# UART_MUX.net
KiCad netlist of a schematic drawn in Altium Designer
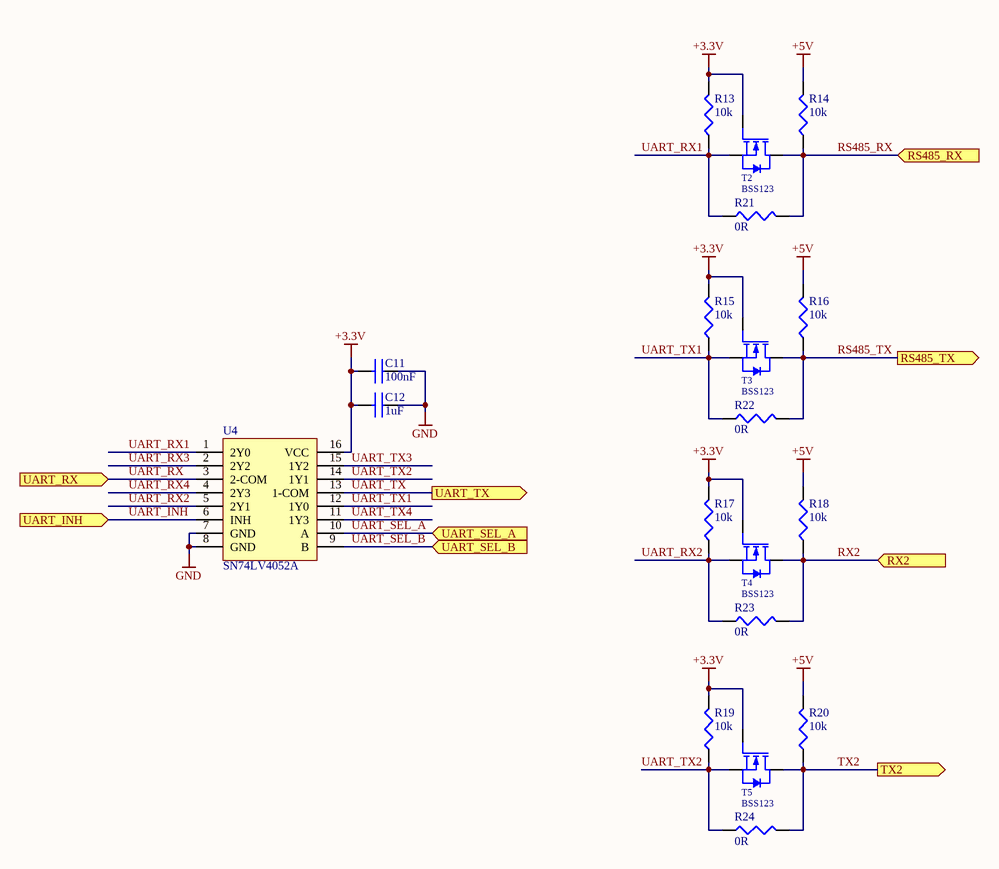
[diagram p0: UART_MUX.SchDoc]

(export (version "E")
  (design (tool "Eeschema 10.0.6"))
  (components
    (comp (ref "C11")
      (value "100nF")
      (footprint "CAP0603")
      (description "MURATA - GRM188R71C104KA01J - CAP, MLCC, X7R, 0.1UF, 16V, 0603")
      (fields
        (field (name "MANUFACTURER") "MURATA")
        (field (name "MANUFACTURER PART NUMBER") "GRM188R71C104KA01J")
      )
      (libsource (lib "Passive") (part "C - 100nF"))
    )
    (comp (ref "C12")
      (value "1uF")
      (footprint "CAP0603")
      (description "MURATA - GRM188R61H105KAALD - CAP, MLCC, X5R, 1UF, 50V, 0603")
      (fields
        (field (name "MANUFACTURER") "MURATA")
        (field (name "MANUFACTURER PART NUMBER") "GRM188R61H105KAALD")
      )
      (libsource (lib "Passive") (part "C - 1uF"))
    )
    (comp (ref "R13")
      (value "10k")
      (footprint "RES0603")
      (description "MULTICOMP - MCMR06X103 JTL - RES, CERAMIC, 10K, 5%, 0.1W, 0603")
      (fields
        (field (name "MANUFACTURER") "MULTICOMP")
        (field (name "MANUFACTURER PART NUMBER") "MCMR06X103 JTL")
      )
      (libsource (lib "Passive") (part "R - 10k"))
    )
    (comp (ref "R14")
      (value "10k")
      (footprint "RES0603")
      (description "MULTICOMP - MCMR06X103 JTL - RES, CERAMIC, 10K, 5%, 0.1W, 0603")
      (fields
        (field (name "MANUFACTURER") "MULTICOMP")
        (field (name "MANUFACTURER PART NUMBER") "MCMR06X103 JTL")
      )
      (libsource (lib "Passive") (part "R - 10k"))
    )
    (comp (ref "R15")
      (value "10k")
      (footprint "RES0603")
      (description "MULTICOMP - MCMR06X103 JTL - RES, CERAMIC, 10K, 5%, 0.1W, 0603")
      (fields
        (field (name "MANUFACTURER") "MULTICOMP")
        (field (name "MANUFACTURER PART NUMBER") "MCMR06X103 JTL")
      )
      (libsource (lib "Passive") (part "R - 10k"))
    )
    (comp (ref "R16")
      (value "10k")
      (footprint "RES0603")
      (description "MULTICOMP - MCMR06X103 JTL - RES, CERAMIC, 10K, 5%, 0.1W, 0603")
      (fields
        (field (name "MANUFACTURER") "MULTICOMP")
        (field (name "MANUFACTURER PART NUMBER") "MCMR06X103 JTL")
      )
      (libsource (lib "Passive") (part "R - 10k"))
    )
    (comp (ref "R17")
      (value "10k")
      (footprint "RES0603")
      (description "MULTICOMP - MCMR06X103 JTL - RES, CERAMIC, 10K, 5%, 0.1W, 0603")
      (fields
        (field (name "MANUFACTURER") "MULTICOMP")
        (field (name "MANUFACTURER PART NUMBER") "MCMR06X103 JTL")
      )
      (libsource (lib "Passive") (part "R - 10k"))
    )
    (comp (ref "R18")
      (value "10k")
      (footprint "RES0603")
      (description "MULTICOMP - MCMR06X103 JTL - RES, CERAMIC, 10K, 5%, 0.1W, 0603")
      (fields
        (field (name "MANUFACTURER") "MULTICOMP")
        (field (name "MANUFACTURER PART NUMBER") "MCMR06X103 JTL")
      )
      (libsource (lib "Passive") (part "R - 10k"))
    )
    (comp (ref "R19")
      (value "10k")
      (footprint "RES0603")
      (description "MULTICOMP - MCMR06X103 JTL - RES, CERAMIC, 10K, 5%, 0.1W, 0603")
      (fields
        (field (name "MANUFACTURER") "MULTICOMP")
        (field (name "MANUFACTURER PART NUMBER") "MCMR06X103 JTL")
      )
      (libsource (lib "Passive") (part "R - 10k"))
    )
    (comp (ref "R20")
      (value "10k")
      (footprint "RES0603")
      (description "MULTICOMP - MCMR06X103 JTL - RES, CERAMIC, 10K, 5%, 0.1W, 0603")
      (fields
        (field (name "MANUFACTURER") "MULTICOMP")
        (field (name "MANUFACTURER PART NUMBER") "MCMR06X103 JTL")
      )
      (libsource (lib "Passive") (part "R - 10k"))
    )
    (comp (ref "R21")
      (value "0R")
      (footprint "RES0603")
      (description "BOURNS - CR0603-J/-000ELF - RES, THICK FILM, 0R, 5%, 0.1W, 0603")
      (fields
        (field (name "MANUFACTURER") "BOURNS")
        (field (name "MANUFACTURER PART NUMBER") "CR0603-J/-000ELF")
      )
      (libsource (lib "Passive") (part "R - 0R"))
    )
    (comp (ref "R22")
      (value "0R")
      (footprint "RES0603")
      (description "BOURNS - CR0603-J/-000ELF - RES, THICK FILM, 0R, 5%, 0.1W, 0603")
      (fields
        (field (name "MANUFACTURER") "BOURNS")
        (field (name "MANUFACTURER PART NUMBER") "CR0603-J/-000ELF")
      )
      (libsource (lib "Passive") (part "R - 0R"))
    )
    (comp (ref "R23")
      (value "0R")
      (footprint "RES0603")
      (description "BOURNS - CR0603-J/-000ELF - RES, THICK FILM, 0R, 5%, 0.1W, 0603")
      (fields
        (field (name "MANUFACTURER") "BOURNS")
        (field (name "MANUFACTURER PART NUMBER") "CR0603-J/-000ELF")
      )
      (libsource (lib "Passive") (part "R - 0R"))
    )
    (comp (ref "R24")
      (value "0R")
      (footprint "RES0603")
      (description "BOURNS - CR0603-J/-000ELF - RES, THICK FILM, 0R, 5%, 0.1W, 0603")
      (fields
        (field (name "MANUFACTURER") "BOURNS")
        (field (name "MANUFACTURER PART NUMBER") "CR0603-J/-000ELF")
      )
      (libsource (lib "Passive") (part "R - 0R"))
    )
    (comp (ref "T2")
      (value "BSS123")
      (footprint "Active:SOT23-3AL")
      (description "N-Channel Vds = 100V, Id = 170 mA")
      (libsource (lib "Active") (part "T_M - BSS123"))
    )
    (comp (ref "T3")
      (value "BSS123")
      (footprint "Active:SOT23-3AL")
      (description "N-Channel Vds = 100V, Id = 170 mA")
      (libsource (lib "Active") (part "T_M - BSS123"))
    )
    (comp (ref "T4")
      (value "BSS123")
      (footprint "Active:SOT23-3AL")
      (description "N-Channel Vds = 100V, Id = 170 mA")
      (libsource (lib "Active") (part "T_M - BSS123"))
    )
    (comp (ref "T5")
      (value "BSS123")
      (footprint "Active:SOT23-3AL")
      (description "N-Channel Vds = 100V, Id = 170 mA")
      (libsource (lib "Active") (part "T_M - BSS123"))
    )
    (comp (ref "U4")
      (value "SN74LV4052A")
      (footprint "SOIC-16")
      (description "Analog Multiplexer/Demultiplexer, 4:1, 2 Circuits, 100ohm, 2V to 5.5V Supply, SOIC-16")
      (libsource (lib "Active") (part "INT - SN74LV4052A"))
    )
  )
  (nets
    (net (code "1") (name "+3.3V") (class "Default")
      (node (ref "C11") (pin "2") (pinfunction "2_2") (pintype "passive"))
      (node (ref "C12") (pin "2") (pinfunction "2_2") (pintype "passive"))
      (node (ref "R13") (pin "2") (pinfunction "2_2") (pintype "passive"))
      (node (ref "R15") (pin "2") (pinfunction "2_2") (pintype "passive"))
      (node (ref "R17") (pin "2") (pinfunction "2_2") (pintype "passive"))
      (node (ref "R19") (pin "2") (pinfunction "2_2") (pintype "passive"))
      (node (ref "T2") (pin "1") (pinfunction "G_1") (pintype "passive"))
      (node (ref "T3") (pin "1") (pinfunction "G_1") (pintype "passive"))
      (node (ref "T4") (pin "1") (pinfunction "G_1") (pintype "passive"))
      (node (ref "T5") (pin "1") (pinfunction "G_1") (pintype "passive"))
      (node (ref "U4") (pin "16") (pinfunction "VCC_16") (pintype "passive"))
    )
    (net (code "2") (name "+5V") (class "Default")
      (node (ref "R14") (pin "2") (pinfunction "2_2") (pintype "passive"))
      (node (ref "R16") (pin "2") (pinfunction "2_2") (pintype "passive"))
      (node (ref "R18") (pin "2") (pinfunction "2_2") (pintype "passive"))
      (node (ref "R20") (pin "2") (pinfunction "2_2") (pintype "passive"))
    )
    (net (code "3") (name "/RS485_RX") (class "Default")
      (node (ref "R14") (pin "1") (pinfunction "1_1") (pintype "passive"))
      (node (ref "R21") (pin "2") (pinfunction "2_2") (pintype "passive"))
      (node (ref "T2") (pin "3") (pinfunction "D_3") (pintype "passive"))
    )
    (net (code "4") (name "/RS485_TX") (class "Default")
      (node (ref "R16") (pin "1") (pinfunction "1_1") (pintype "passive"))
      (node (ref "R22") (pin "2") (pinfunction "2_2") (pintype "passive"))
      (node (ref "T3") (pin "3") (pinfunction "D_3") (pintype "passive"))
    )
    (net (code "5") (name "/RX2") (class "Default")
      (node (ref "R18") (pin "1") (pinfunction "1_1") (pintype "passive"))
      (node (ref "R23") (pin "2") (pinfunction "2_2") (pintype "passive"))
      (node (ref "T4") (pin "3") (pinfunction "D_3") (pintype "passive"))
    )
    (net (code "6") (name "/TX2") (class "Default")
      (node (ref "R20") (pin "1") (pinfunction "1_1") (pintype "passive"))
      (node (ref "R24") (pin "2") (pinfunction "2_2") (pintype "passive"))
      (node (ref "T5") (pin "3") (pinfunction "D_3") (pintype "passive"))
    )
    (net (code "7") (name "/UART_INH") (class "Default")
      (node (ref "U4") (pin "6") (pinfunction "INH_6") (pintype "passive"))
    )
    (net (code "8") (name "/UART_RX") (class "Default")
      (node (ref "U4") (pin "3") (pinfunction "2-COM_3") (pintype "passive"))
    )
    (net (code "9") (name "/UART_RX1") (class "Default")
      (node (ref "R13") (pin "1") (pinfunction "1_1") (pintype "passive"))
      (node (ref "R21") (pin "1") (pinfunction "1_1") (pintype "passive"))
      (node (ref "T2") (pin "2") (pinfunction "S_2") (pintype "passive"))
      (node (ref "U4") (pin "1") (pinfunction "2Y0_1") (pintype "passive"))
    )
    (net (code "10") (name "/UART_RX2") (class "Default")
      (node (ref "R17") (pin "1") (pinfunction "1_1") (pintype "passive"))
      (node (ref "R23") (pin "1") (pinfunction "1_1") (pintype "passive"))
      (node (ref "T4") (pin "2") (pinfunction "S_2") (pintype "passive"))
      (node (ref "U4") (pin "5") (pinfunction "2Y1_5") (pintype "passive"))
    )
    (net (code "11") (name "/UART_RX3") (class "Default")
      (node (ref "U4") (pin "2") (pinfunction "2Y2_2") (pintype "passive"))
    )
    (net (code "12") (name "/UART_RX4") (class "Default")
      (node (ref "U4") (pin "4") (pinfunction "2Y3_4") (pintype "passive"))
    )
    (net (code "13") (name "/UART_SEL_A") (class "Default")
      (node (ref "U4") (pin "10") (pinfunction "A_10") (pintype "passive"))
    )
    (net (code "14") (name "/UART_SEL_B") (class "Default")
      (node (ref "U4") (pin "9") (pinfunction "B_9") (pintype "passive"))
    )
    (net (code "15") (name "/UART_TX") (class "Default")
      (node (ref "U4") (pin "13") (pinfunction "1-COM_13") (pintype "passive"))
    )
    (net (code "16") (name "/UART_TX1") (class "Default")
      (node (ref "R15") (pin "1") (pinfunction "1_1") (pintype "passive"))
      (node (ref "R22") (pin "1") (pinfunction "1_1") (pintype "passive"))
      (node (ref "T3") (pin "2") (pinfunction "S_2") (pintype "passive"))
      (node (ref "U4") (pin "12") (pinfunction "1Y0_12") (pintype "passive"))
    )
    (net (code "17") (name "/UART_TX2") (class "Default")
      (node (ref "R19") (pin "1") (pinfunction "1_1") (pintype "passive"))
      (node (ref "R24") (pin "1") (pinfunction "1_1") (pintype "passive"))
      (node (ref "T5") (pin "2") (pinfunction "S_2") (pintype "passive"))
      (node (ref "U4") (pin "14") (pinfunction "1Y1_14") (pintype "passive"))
    )
    (net (code "18") (name "/UART_TX3") (class "Default")
      (node (ref "U4") (pin "15") (pinfunction "1Y2_15") (pintype "passive"))
    )
    (net (code "19") (name "/UART_TX4") (class "Default")
      (node (ref "U4") (pin "11") (pinfunction "1Y3_11") (pintype "passive"))
    )
    (net (code "20") (name "GND") (class "Default")
      (node (ref "C11") (pin "1") (pinfunction "1_1") (pintype "passive"))
      (node (ref "C12") (pin "1") (pinfunction "1_1") (pintype "passive"))
      (node (ref "U4") (pin "7") (pinfunction "GND_7") (pintype "passive"))
      (node (ref "U4") (pin "8") (pinfunction "GND_8") (pintype "passive"))
    )
  )
)
